# tst_proj.net
KiCad netlist of a schematic drawn in EasyEDA
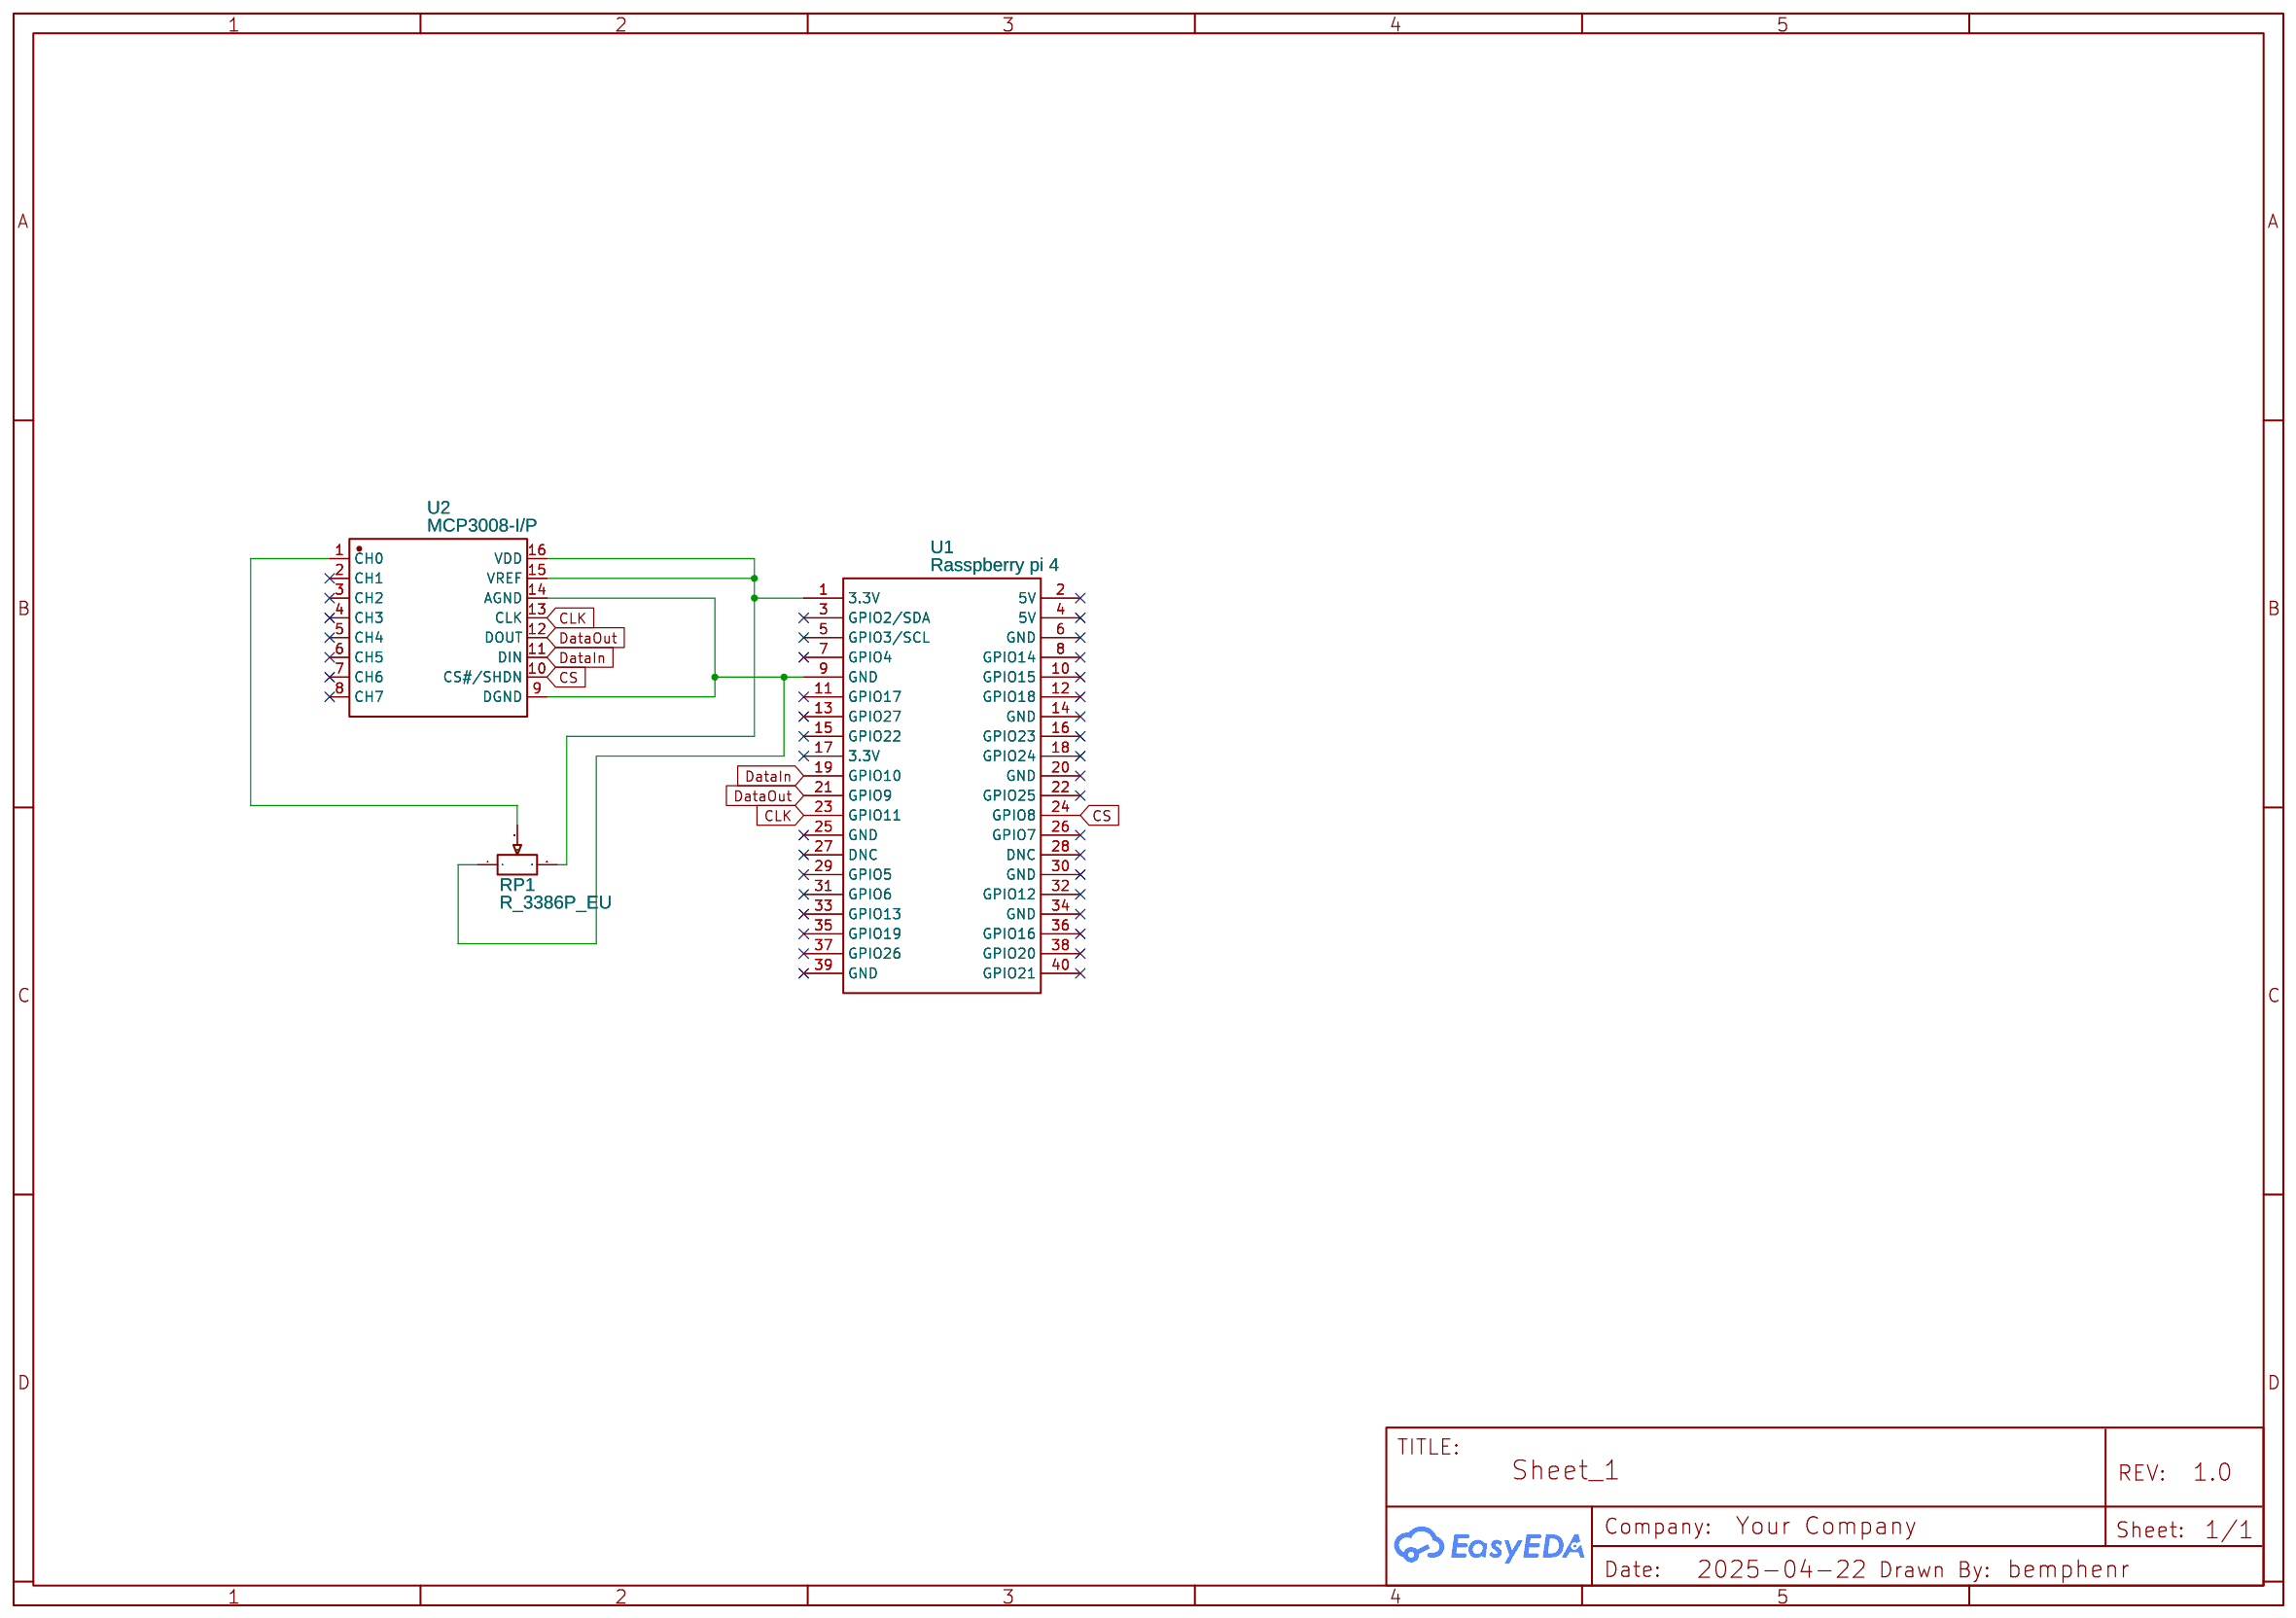
[diagram p0: schematic sheet]

(export (version "E")
  (design (tool "Eeschema 10.0.6"))
  (components
    (comp (ref "RP1") (value "R_3386P_EU") (libsource (lib "") (part "R_3386P_EU")))
    (comp (ref "U1") (value "Rasspberry pi 4") (libsource (lib "") (part "Rasspberry pi 4")))
    (comp (ref "U2")
      (value "MCP3008-I/P")
      (fields (field (name "Manufacturer") "MICROCHIP(美国微芯)"))
      (libsource (lib "") (part "MCP3008-I/P"))
    )
  )
  (nets
    (net (code "1") (name "CLK") (class "Default")
      (node (ref "U1") (pin "23") (pinfunction "GPIO11_23") (pintype "bidirectional"))
      (node (ref "U2") (pin "13") (pinfunction "CLK_13") (pintype "unspecified"))
    )
    (net (code "2") (name "CS") (class "Default")
      (node (ref "U1") (pin "24") (pinfunction "GPIO8_24") (pintype "bidirectional"))
      (node (ref "U2") (pin "10") (pinfunction "CS#/SHDN_10") (pintype "unspecified"))
    )
    (net (code "3") (name "DataIn") (class "Default")
      (node (ref "U1") (pin "19") (pinfunction "GPIO10_19") (pintype "bidirectional"))
      (node (ref "U2") (pin "11") (pinfunction "DIN_11") (pintype "unspecified"))
    )
    (net (code "4") (name "DataOut") (class "Default")
      (node (ref "U1") (pin "21") (pinfunction "GPIO9_21") (pintype "bidirectional"))
      (node (ref "U2") (pin "12") (pinfunction "DOUT_12") (pintype "unspecified"))
    )
    (net (code "5") (name "Net-(U2-AGND)") (class "Default")
      (node (ref "RP1") (pin "1") (pinfunction "1_1") (pintype "input"))
      (node (ref "U1") (pin "9") (pinfunction "GND_9") (pintype "unspecified"))
      (node (ref "U2") (pin "14") (pinfunction "AGND_14") (pintype "unspecified"))
      (node (ref "U2") (pin "9") (pinfunction "DGND_9") (pintype "unspecified"))
    )
    (net (code "6") (name "Net-(U2-CH0)") (class "Default")
      (node (ref "RP1") (pin "2") (pinfunction "2_2") (pintype "input"))
      (node (ref "U2") (pin "1") (pinfunction "CH0_1") (pintype "unspecified"))
    )
    (net (code "7") (name "Net-(U2-VDD)") (class "Default")
      (node (ref "RP1") (pin "3") (pinfunction "3_3") (pintype "input"))
      (node (ref "U1") (pin "1") (pinfunction "3.3V_1") (pintype "passive"))
      (node (ref "U2") (pin "15") (pinfunction "VREF_15") (pintype "unspecified"))
      (node (ref "U2") (pin "16") (pinfunction "VDD_16") (pintype "unspecified"))
    )
    (net (code "8") (name "unconnected-(U1-3.3V-Pad17)") (class "Default")
      (node (ref "U1") (pin "17") (pinfunction "3.3V_17") (pintype "passive+no_connect"))
    )
    (net (code "9") (name "unconnected-(U1-5V-Pad2)") (class "Default")
      (node (ref "U1") (pin "2") (pinfunction "5V_2") (pintype "passive+no_connect"))
    )
    (net (code "10") (name "unconnected-(U1-5V-Pad4)") (class "Default")
      (node (ref "U1") (pin "4") (pinfunction "5V_4") (pintype "passive+no_connect"))
    )
    (net (code "11") (name "unconnected-(U1-DNC-Pad27)") (class "Default")
      (node (ref "U1") (pin "27") (pinfunction "DNC_27") (pintype "unspecified+no_connect"))
    )
    (net (code "12") (name "unconnected-(U1-DNC-Pad28)") (class "Default")
      (node (ref "U1") (pin "28") (pinfunction "DNC_28") (pintype "unspecified+no_connect"))
    )
    (net (code "13") (name "unconnected-(U1-GND-Pad6)") (class "Default")
      (node (ref "U1") (pin "6") (pinfunction "GND_6") (pintype "unspecified+no_connect"))
    )
    (net (code "14") (name "unconnected-(U1-GND-Pad14)") (class "Default")
      (node (ref "U1") (pin "14") (pinfunction "GND_14") (pintype "unspecified+no_connect"))
    )
    (net (code "15") (name "unconnected-(U1-GND-Pad20)") (class "Default")
      (node (ref "U1") (pin "20") (pinfunction "GND_20") (pintype "unspecified+no_connect"))
    )
    (net (code "16") (name "unconnected-(U1-GND-Pad25)") (class "Default")
      (node (ref "U1") (pin "25") (pinfunction "GND_25") (pintype "unspecified+no_connect"))
    )
    (net (code "17") (name "unconnected-(U1-GND-Pad30)") (class "Default")
      (node (ref "U1") (pin "30") (pinfunction "GND_30") (pintype "unspecified+no_connect"))
    )
    (net (code "18") (name "unconnected-(U1-GND-Pad34)") (class "Default")
      (node (ref "U1") (pin "34") (pinfunction "GND_34") (pintype "unspecified+no_connect"))
    )
    (net (code "19") (name "unconnected-(U1-GND-Pad39)") (class "Default")
      (node (ref "U1") (pin "39") (pinfunction "GND_39") (pintype "unspecified+no_connect"))
    )
    (net (code "20") (name "unconnected-(U1-GPIO2{slash}SDA-Pad3)") (class "Default")
      (node (ref "U1") (pin "3") (pinfunction "GPIO2/SDA_3") (pintype "bidirectional+no_connect"))
    )
    (net (code "21") (name "unconnected-(U1-GPIO3{slash}SCL-Pad5)") (class "Default")
      (node (ref "U1") (pin "5") (pinfunction "GPIO3/SCL_5") (pintype "bidirectional+no_connect"))
    )
    (net (code "22") (name "unconnected-(U1-GPIO4-Pad7)") (class "Default")
      (node (ref "U1") (pin "7") (pinfunction "GPIO4_7") (pintype "bidirectional+no_connect"))
    )
    (net (code "23") (name "unconnected-(U1-GPIO5-Pad29)") (class "Default")
      (node (ref "U1") (pin "29") (pinfunction "GPIO5_29") (pintype "bidirectional+no_connect"))
    )
    (net (code "24") (name "unconnected-(U1-GPIO6-Pad31)") (class "Default")
      (node (ref "U1") (pin "31") (pinfunction "GPIO6_31") (pintype "bidirectional+no_connect"))
    )
    (net (code "25") (name "unconnected-(U1-GPIO7-Pad26)") (class "Default")
      (node (ref "U1") (pin "26") (pinfunction "GPIO7_26") (pintype "bidirectional+no_connect"))
    )
    (net (code "26") (name "unconnected-(U1-GPIO12-Pad32)") (class "Default")
      (node (ref "U1") (pin "32") (pinfunction "GPIO12_32") (pintype "bidirectional+no_connect"))
    )
    (net (code "27") (name "unconnected-(U1-GPIO13-Pad33)") (class "Default")
      (node (ref "U1") (pin "33") (pinfunction "GPIO13_33") (pintype "bidirectional+no_connect"))
    )
    (net (code "28") (name "unconnected-(U1-GPIO14-Pad8)") (class "Default")
      (node (ref "U1") (pin "8") (pinfunction "GPIO14_8") (pintype "bidirectional+no_connect"))
    )
    (net (code "29") (name "unconnected-(U1-GPIO15-Pad10)") (class "Default")
      (node (ref "U1") (pin "10") (pinfunction "GPIO15_10") (pintype "bidirectional+no_connect"))
    )
    (net (code "30") (name "unconnected-(U1-GPIO16-Pad36)") (class "Default")
      (node (ref "U1") (pin "36") (pinfunction "GPIO16_36") (pintype "bidirectional+no_connect"))
    )
    (net (code "31") (name "unconnected-(U1-GPIO17-Pad11)") (class "Default")
      (node (ref "U1") (pin "11") (pinfunction "GPIO17_11") (pintype "bidirectional+no_connect"))
    )
    (net (code "32") (name "unconnected-(U1-GPIO18-Pad12)") (class "Default")
      (node (ref "U1") (pin "12") (pinfunction "GPIO18_12") (pintype "bidirectional+no_connect"))
    )
    (net (code "33") (name "unconnected-(U1-GPIO19-Pad35)") (class "Default")
      (node (ref "U1") (pin "35") (pinfunction "GPIO19_35") (pintype "bidirectional+no_connect"))
    )
    (net (code "34") (name "unconnected-(U1-GPIO20-Pad38)") (class "Default")
      (node (ref "U1") (pin "38") (pinfunction "GPIO20_38") (pintype "bidirectional+no_connect"))
    )
    (net (code "35") (name "unconnected-(U1-GPIO21-Pad40)") (class "Default")
      (node (ref "U1") (pin "40") (pinfunction "GPIO21_40") (pintype "bidirectional+no_connect"))
    )
    (net (code "36") (name "unconnected-(U1-GPIO22-Pad15)") (class "Default")
      (node (ref "U1") (pin "15") (pinfunction "GPIO22_15") (pintype "bidirectional+no_connect"))
    )
    (net (code "37") (name "unconnected-(U1-GPIO23-Pad16)") (class "Default")
      (node (ref "U1") (pin "16") (pinfunction "GPIO23_16") (pintype "bidirectional+no_connect"))
    )
    (net (code "38") (name "unconnected-(U1-GPIO24-Pad18)") (class "Default")
      (node (ref "U1") (pin "18") (pinfunction "GPIO24_18") (pintype "bidirectional+no_connect"))
    )
    (net (code "39") (name "unconnected-(U1-GPIO25-Pad22)") (class "Default")
      (node (ref "U1") (pin "22") (pinfunction "GPIO25_22") (pintype "bidirectional+no_connect"))
    )
    (net (code "40") (name "unconnected-(U1-GPIO26-Pad37)") (class "Default")
      (node (ref "U1") (pin "37") (pinfunction "GPIO26_37") (pintype "bidirectional+no_connect"))
    )
    (net (code "41") (name "unconnected-(U1-GPIO27-Pad13)") (class "Default")
      (node (ref "U1") (pin "13") (pinfunction "GPIO27_13") (pintype "bidirectional+no_connect"))
    )
    (net (code "42") (name "unconnected-(U2-CH1-Pad2)") (class "Default")
      (node (ref "U2") (pin "2") (pinfunction "CH1_2") (pintype "unspecified+no_connect"))
    )
    (net (code "43") (name "unconnected-(U2-CH2-Pad3)") (class "Default")
      (node (ref "U2") (pin "3") (pinfunction "CH2_3") (pintype "unspecified+no_connect"))
    )
    (net (code "44") (name "unconnected-(U2-CH3-Pad4)") (class "Default")
      (node (ref "U2") (pin "4") (pinfunction "CH3_4") (pintype "unspecified+no_connect"))
    )
    (net (code "45") (name "unconnected-(U2-CH4-Pad5)") (class "Default")
      (node (ref "U2") (pin "5") (pinfunction "CH4_5") (pintype "unspecified+no_connect"))
    )
    (net (code "46") (name "unconnected-(U2-CH5-Pad6)") (class "Default")
      (node (ref "U2") (pin "6") (pinfunction "CH5_6") (pintype "unspecified+no_connect"))
    )
    (net (code "47") (name "unconnected-(U2-CH6-Pad7)") (class "Default")
      (node (ref "U2") (pin "7") (pinfunction "CH6_7") (pintype "unspecified+no_connect"))
    )
    (net (code "48") (name "unconnected-(U2-CH7-Pad8)") (class "Default")
      (node (ref "U2") (pin "8") (pinfunction "CH7_8") (pintype "unspecified+no_connect"))
    )
  )
)
